# dcc_block_detector.net
KiCad netlist of a schematic drawn in EAGLE
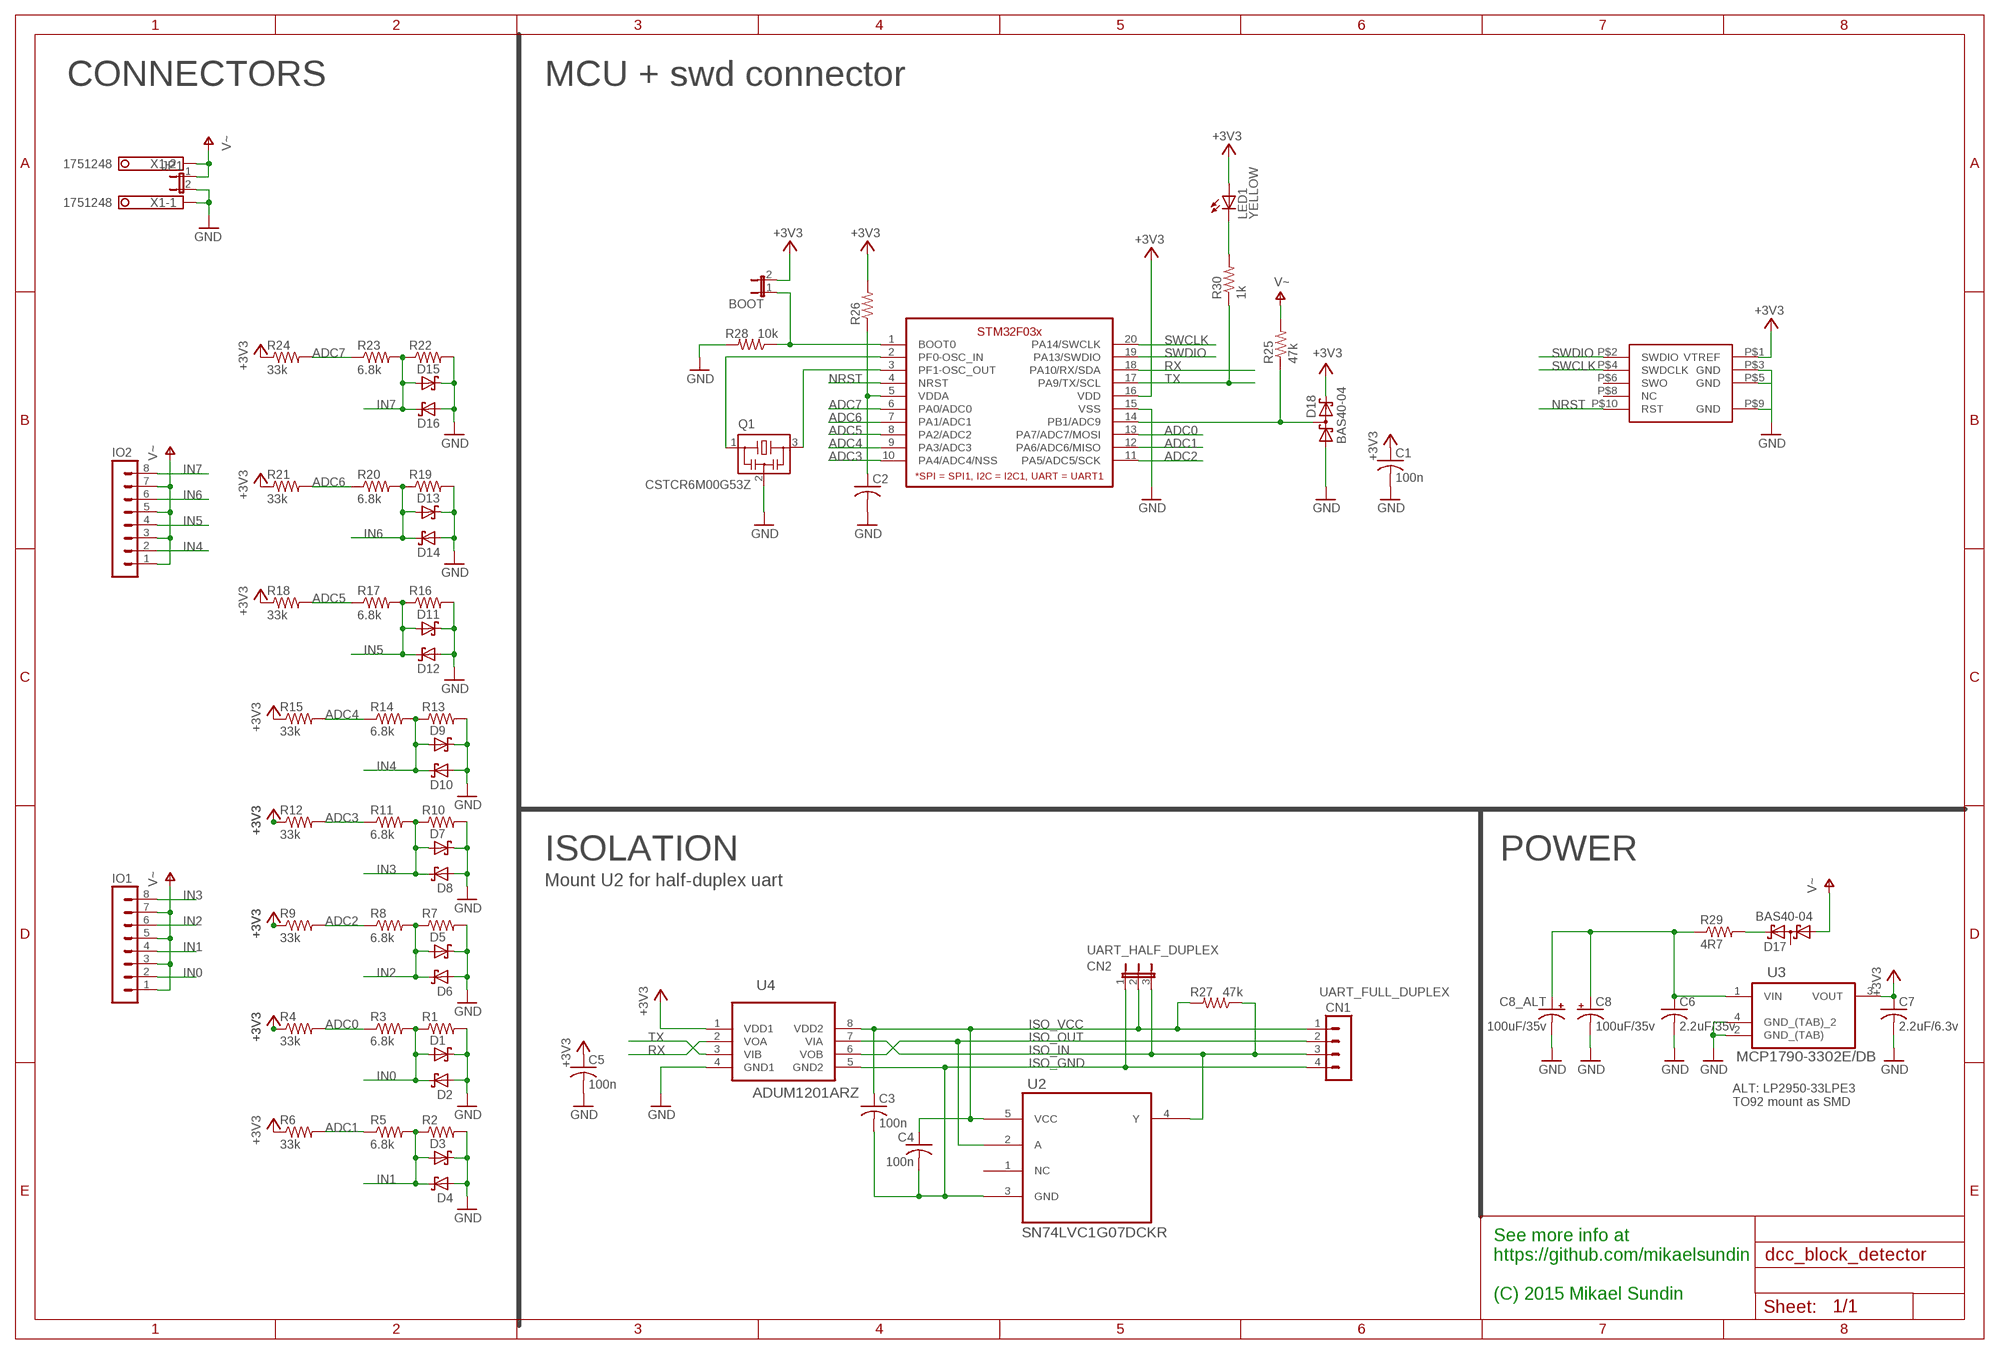
[diagram p0: schematic, sheet 1]

(export (version "E")
  (design (tool "Eeschema 10.0.6"))
  (components
    (comp (ref "BOOT")
      (value "JP1E")
      (footprint "eagle-import:JP1")
      (libsource (lib "eagle-import") (part "JP1E"))
    )
    (comp (ref "C1")
      (value "100n")
      (footprint "eagle-import:C0603")
      (libsource (lib "eagle-import") (part "C-USC0603"))
    )
    (comp (ref "C2")
      (value "C-USC0603")
      (footprint "eagle-import:C0603")
      (libsource (lib "eagle-import") (part "C-USC0603"))
    )
    (comp (ref "C3")
      (value "100n")
      (footprint "eagle-import:C0603")
      (libsource (lib "eagle-import") (part "C-USC0603"))
    )
    (comp (ref "C4")
      (value "100n")
      (footprint "eagle-import:C0603")
      (libsource (lib "eagle-import") (part "C-USC0603"))
    )
    (comp (ref "C5")
      (value "100n")
      (footprint "eagle-import:C0603")
      (libsource (lib "eagle-import") (part "C-USC0603"))
    )
    (comp (ref "C6")
      (value "2.2uF/35v")
      (footprint "eagle-import:C0805")
      (libsource (lib "eagle-import") (part "C-USC0805"))
    )
    (comp (ref "C7")
      (value "2.2uF/6.3v")
      (footprint "eagle-import:C0805")
      (libsource (lib "eagle-import") (part "C-USC0805"))
    )
    (comp (ref "C8")
      (value "100uF/35v")
      (footprint "eagle-import:UD-6,3X7,7_NICHICON")
      (libsource (lib "eagle-import") (part "CPOL-USUD-6,3X7,7"))
    )
    (comp (ref "C8_ALT")
      (value "100uF/35v")
      (footprint "eagle-import:E2,5-6")
      (libsource (lib "eagle-import") (part "CPOL-USE2.5-6"))
    )
    (comp (ref "CN1")
      (value "UART_FULL_DUPLEX")
      (footprint "eagle-import:MA04-1")
      (libsource (lib "eagle-import") (part "MA04-1"))
    )
    (comp (ref "CN2")
      (value "UART_HALF_DUPLEX")
      (footprint "eagle-import:JP2")
      (libsource (lib "eagle-import") (part "JP2E"))
    )
    (comp (ref "D1")
      (value "SCHOTTKY-DIODESMC")
      (footprint "eagle-import:SMC")
      (libsource (lib "eagle-import") (part "SCHOTTKY-DIODESMC"))
    )
    (comp (ref "D2")
      (value "SCHOTTKY-DIODESMC")
      (footprint "eagle-import:SMC")
      (libsource (lib "eagle-import") (part "SCHOTTKY-DIODESMC"))
    )
    (comp (ref "D3")
      (value "SCHOTTKY-DIODESMC")
      (footprint "eagle-import:SMC")
      (libsource (lib "eagle-import") (part "SCHOTTKY-DIODESMC"))
    )
    (comp (ref "D4")
      (value "SCHOTTKY-DIODESMC")
      (footprint "eagle-import:SMC")
      (libsource (lib "eagle-import") (part "SCHOTTKY-DIODESMC"))
    )
    (comp (ref "D5")
      (value "SCHOTTKY-DIODESMC")
      (footprint "eagle-import:SMC")
      (libsource (lib "eagle-import") (part "SCHOTTKY-DIODESMC"))
    )
    (comp (ref "D6")
      (value "SCHOTTKY-DIODESMC")
      (footprint "eagle-import:SMC")
      (libsource (lib "eagle-import") (part "SCHOTTKY-DIODESMC"))
    )
    (comp (ref "D7")
      (value "SCHOTTKY-DIODESMC")
      (footprint "eagle-import:SMC")
      (libsource (lib "eagle-import") (part "SCHOTTKY-DIODESMC"))
    )
    (comp (ref "D8")
      (value "SCHOTTKY-DIODESMC")
      (footprint "eagle-import:SMC")
      (libsource (lib "eagle-import") (part "SCHOTTKY-DIODESMC"))
    )
    (comp (ref "D9")
      (value "SCHOTTKY-DIODESMC")
      (footprint "eagle-import:SMC")
      (libsource (lib "eagle-import") (part "SCHOTTKY-DIODESMC"))
    )
    (comp (ref "D10")
      (value "SCHOTTKY-DIODESMC")
      (footprint "eagle-import:SMC")
      (libsource (lib "eagle-import") (part "SCHOTTKY-DIODESMC"))
    )
    (comp (ref "D11")
      (value "SCHOTTKY-DIODESMC")
      (footprint "eagle-import:SMC")
      (libsource (lib "eagle-import") (part "SCHOTTKY-DIODESMC"))
    )
    (comp (ref "D12")
      (value "SCHOTTKY-DIODESMC")
      (footprint "eagle-import:SMC")
      (libsource (lib "eagle-import") (part "SCHOTTKY-DIODESMC"))
    )
    (comp (ref "D13")
      (value "SCHOTTKY-DIODESMC")
      (footprint "eagle-import:SMC")
      (libsource (lib "eagle-import") (part "SCHOTTKY-DIODESMC"))
    )
    (comp (ref "D14")
      (value "SCHOTTKY-DIODESMC")
      (footprint "eagle-import:SMC")
      (libsource (lib "eagle-import") (part "SCHOTTKY-DIODESMC"))
    )
    (comp (ref "D15")
      (value "SCHOTTKY-DIODESMC")
      (footprint "eagle-import:SMC")
      (libsource (lib "eagle-import") (part "SCHOTTKY-DIODESMC"))
    )
    (comp (ref "D16")
      (value "SCHOTTKY-DIODESMC")
      (footprint "eagle-import:SMC")
      (libsource (lib "eagle-import") (part "SCHOTTKY-DIODESMC"))
    )
    (comp (ref "D17")
      (value "BAS40-04")
      (footprint "eagle-import:SOT23")
      (libsource (lib "eagle-import") (part "BAS40-04"))
    )
    (comp (ref "D18")
      (value "BAS40-04")
      (footprint "eagle-import:SOT23")
      (libsource (lib "eagle-import") (part "BAS40-04"))
    )
    (comp (ref "IO1")
      (value "MA08-1W")
      (footprint "eagle-import:MA08-1W")
      (libsource (lib "eagle-import") (part "MA08-1W"))
    )
    (comp (ref "IO2")
      (value "MA08-1W")
      (footprint "eagle-import:MA08-1W")
      (libsource (lib "eagle-import") (part "MA08-1W"))
    )
    (comp (ref "JP1")
      (value "JP1E")
      (footprint "eagle-import:JP1")
      (libsource (lib "eagle-import") (part "JP1E"))
    )
    (comp (ref "LED1")
      (value "YELLOW")
      (footprint "eagle-import:CHIPLED_0603")
      (libsource (lib "eagle-import") (part "LEDCHIPLED_0603"))
    )
    (comp (ref "Q1")
      (value "CSTCR6M00G53Z")
      (footprint "eagle-import:CSTER12M")
      (fields (field (name "MPN") "CSTCC12M0"))
      (libsource (lib "eagle-import") (part "CSTCR6M00G53Z"))
    )
    (comp (ref "R1")
      (value "R-US_R1206")
      (footprint "eagle-import:R1206")
      (libsource (lib "eagle-import") (part "R-US_R1206"))
    )
    (comp (ref "R2")
      (value "R-US_R1206")
      (footprint "eagle-import:R1206")
      (libsource (lib "eagle-import") (part "R-US_R1206"))
    )
    (comp (ref "R3")
      (value "6.8k")
      (footprint "eagle-import:R0603")
      (libsource (lib "eagle-import") (part "R-US_R0603"))
    )
    (comp (ref "R4")
      (value "33k")
      (footprint "eagle-import:R0603")
      (libsource (lib "eagle-import") (part "R-US_R0603"))
    )
    (comp (ref "R5")
      (value "6.8k")
      (footprint "eagle-import:R0603")
      (libsource (lib "eagle-import") (part "R-US_R0603"))
    )
    (comp (ref "R6")
      (value "33k")
      (footprint "eagle-import:R0603")
      (libsource (lib "eagle-import") (part "R-US_R0603"))
    )
    (comp (ref "R7")
      (value "R-US_R1206")
      (footprint "eagle-import:R1206")
      (libsource (lib "eagle-import") (part "R-US_R1206"))
    )
    (comp (ref "R8")
      (value "6.8k")
      (footprint "eagle-import:R0603")
      (libsource (lib "eagle-import") (part "R-US_R0603"))
    )
    (comp (ref "R9")
      (value "33k")
      (footprint "eagle-import:R0603")
      (libsource (lib "eagle-import") (part "R-US_R0603"))
    )
    (comp (ref "R10")
      (value "R-US_R1206")
      (footprint "eagle-import:R1206")
      (libsource (lib "eagle-import") (part "R-US_R1206"))
    )
    (comp (ref "R11")
      (value "6.8k")
      (footprint "eagle-import:R0603")
      (libsource (lib "eagle-import") (part "R-US_R0603"))
    )
    (comp (ref "R12")
      (value "33k")
      (footprint "eagle-import:R0603")
      (libsource (lib "eagle-import") (part "R-US_R0603"))
    )
    (comp (ref "R13")
      (value "R-US_R1206")
      (footprint "eagle-import:R1206")
      (libsource (lib "eagle-import") (part "R-US_R1206"))
    )
    (comp (ref "R14")
      (value "6.8k")
      (footprint "eagle-import:R0603")
      (libsource (lib "eagle-import") (part "R-US_R0603"))
    )
    (comp (ref "R15")
      (value "33k")
      (footprint "eagle-import:R0603")
      (libsource (lib "eagle-import") (part "R-US_R0603"))
    )
    (comp (ref "R16")
      (value "R-US_R1206")
      (footprint "eagle-import:R1206")
      (libsource (lib "eagle-import") (part "R-US_R1206"))
    )
    (comp (ref "R17")
      (value "6.8k")
      (footprint "eagle-import:R0603")
      (libsource (lib "eagle-import") (part "R-US_R0603"))
    )
    (comp (ref "R18")
      (value "33k")
      (footprint "eagle-import:R0603")
      (libsource (lib "eagle-import") (part "R-US_R0603"))
    )
    (comp (ref "R19")
      (value "R-US_R1206")
      (footprint "eagle-import:R1206")
      (libsource (lib "eagle-import") (part "R-US_R1206"))
    )
    (comp (ref "R20")
      (value "6.8k")
      (footprint "eagle-import:R0603")
      (libsource (lib "eagle-import") (part "R-US_R0603"))
    )
    (comp (ref "R21")
      (value "33k")
      (footprint "eagle-import:R0603")
      (libsource (lib "eagle-import") (part "R-US_R0603"))
    )
    (comp (ref "R22")
      (value "R-US_R1206")
      (footprint "eagle-import:R1206")
      (libsource (lib "eagle-import") (part "R-US_R1206"))
    )
    (comp (ref "R23")
      (value "6.8k")
      (footprint "eagle-import:R0603")
      (libsource (lib "eagle-import") (part "R-US_R0603"))
    )
    (comp (ref "R24")
      (value "33k")
      (footprint "eagle-import:R0603")
      (libsource (lib "eagle-import") (part "R-US_R0603"))
    )
    (comp (ref "R25")
      (value "47k")
      (footprint "eagle-import:R0603")
      (libsource (lib "eagle-import") (part "R-US_R0603"))
    )
    (comp (ref "R26")
      (value "R-US_R0603")
      (footprint "eagle-import:R0603")
      (libsource (lib "eagle-import") (part "R-US_R0603"))
    )
    (comp (ref "R27")
      (value "47k")
      (footprint "eagle-import:R0603")
      (libsource (lib "eagle-import") (part "R-US_R0603"))
    )
    (comp (ref "R28")
      (value "10k")
      (footprint "eagle-import:R0603")
      (libsource (lib "eagle-import") (part "R-US_R0603"))
    )
    (comp (ref "R29")
      (value "4R7")
      (footprint "eagle-import:R1206")
      (libsource (lib "eagle-import") (part "R-US_R1206"))
    )
    (comp (ref "R30")
      (value "1k")
      (footprint "eagle-import:R0603")
      (libsource (lib "eagle-import") (part "R-US_R0603"))
    )
    (comp (ref "U$1")
      (value "STM32F03X_TSSOP20")
      (footprint "eagle-import:STM32F03X_TSSOP20")
      (libsource (lib "eagle-import") (part "STM32F03X_TSSOP20"))
    )
    (comp (ref "U$2")
      (value "SWD")
      (footprint "eagle-import:ARM_SWD_2X5")
      (libsource (lib "eagle-import") (part "ARM_SWD_2X5"))
    )
    (comp (ref "U2")
      (value "SN74LVC1G07DCKR")
      (footprint "eagle-import:SOT65P210X110-5N")
      (libsource (lib "eagle-import") (part "SN74LVC1G07DCKR"))
    )
    (comp (ref "U3")
      (value "MCP1790-3302E/DB")
      (footprint "eagle-import:SOT230P700X180-4N")
      (libsource (lib "eagle-import") (part "MCP1790-3302E/DB"))
    )
    (comp (ref "U4")
      (value "ADUM1201ARZ")
      (footprint "eagle-import:SOIC127P600X175-8N")
      (libsource (lib "eagle-import") (part "ADUM1201ARZ"))
    )
    (comp (ref "X1")
      (value "1751248")
      (footprint "eagle-import:1751248")
      (libsource (lib "eagle-import") (part "1751248"))
    )
  )
  (nets
    (net (code "1") (name "+3V3") (class "Default")
      (node (ref "BOOT") (pin "2") (pinfunction "2_2") (pintype "passive"))
      (node (ref "C1") (pin "1") (pinfunction "1_1") (pintype "passive"))
      (node (ref "C5") (pin "1") (pinfunction "1_1") (pintype "passive"))
      (node (ref "C7") (pin "1") (pinfunction "1_1") (pintype "passive"))
      (node (ref "D18") (pin "2") (pinfunction "C2_2") (pintype "passive"))
      (node (ref "LED1") (pin "A") (pinfunction "A_A") (pintype "passive"))
      (node (ref "R12") (pin "1") (pinfunction "1_1") (pintype "passive"))
      (node (ref "R15") (pin "1") (pinfunction "1_1") (pintype "passive"))
      (node (ref "R18") (pin "1") (pinfunction "1_1") (pintype "passive"))
      (node (ref "R21") (pin "1") (pinfunction "1_1") (pintype "passive"))
      (node (ref "R24") (pin "1") (pinfunction "1_1") (pintype "passive"))
      (node (ref "R26") (pin "2") (pinfunction "2_2") (pintype "passive"))
      (node (ref "R4") (pin "1") (pinfunction "1_1") (pintype "passive"))
      (node (ref "R6") (pin "1") (pinfunction "1_1") (pintype "passive"))
      (node (ref "R9") (pin "1") (pinfunction "1_1") (pintype "passive"))
      (node (ref "U$1") (pin "16") (pinfunction "VDD_16") (pintype "output"))
      (node (ref "U$2") (pin "P$1") (pinfunction "VTREF_P$1") (pintype "bidirectional"))
      (node (ref "U3") (pin "3") (pinfunction "VOUT_3") (pintype "output"))
      (node (ref "U4") (pin "1") (pinfunction "VDD1_1") (pintype "power_in"))
    )
    (net (code "2") (name "/ADC0") (class "Default")
      (node (ref "R3") (pin "1") (pinfunction "1_1") (pintype "passive"))
      (node (ref "R4") (pin "2") (pinfunction "2_2") (pintype "passive"))
      (node (ref "U$1") (pin "13") (pinfunction "PA7/ADC7/MOSI_13") (pintype "output"))
    )
    (net (code "3") (name "/ADC1") (class "Default")
      (node (ref "R5") (pin "1") (pinfunction "1_1") (pintype "passive"))
      (node (ref "R6") (pin "2") (pinfunction "2_2") (pintype "passive"))
      (node (ref "U$1") (pin "12") (pinfunction "PA6/ADC6/MISO_12") (pintype "output"))
    )
    (net (code "4") (name "/ADC2") (class "Default")
      (node (ref "R8") (pin "1") (pinfunction "1_1") (pintype "passive"))
      (node (ref "R9") (pin "2") (pinfunction "2_2") (pintype "passive"))
      (node (ref "U$1") (pin "11") (pinfunction "PA5/ADC5/SCK_11") (pintype "output"))
    )
    (net (code "5") (name "/ADC3") (class "Default")
      (node (ref "R11") (pin "1") (pinfunction "1_1") (pintype "passive"))
      (node (ref "R12") (pin "2") (pinfunction "2_2") (pintype "passive"))
      (node (ref "U$1") (pin "10") (pinfunction "PA4/ADC4/NSS_10") (pintype "output"))
    )
    (net (code "6") (name "/ADC4") (class "Default")
      (node (ref "R14") (pin "1") (pinfunction "1_1") (pintype "passive"))
      (node (ref "R15") (pin "2") (pinfunction "2_2") (pintype "passive"))
      (node (ref "U$1") (pin "9") (pinfunction "PA3/ADC3_9") (pintype "output"))
    )
    (net (code "7") (name "/ADC5") (class "Default")
      (node (ref "R17") (pin "1") (pinfunction "1_1") (pintype "passive"))
      (node (ref "R18") (pin "2") (pinfunction "2_2") (pintype "passive"))
      (node (ref "U$1") (pin "8") (pinfunction "PA2/ADC2_8") (pintype "output"))
    )
    (net (code "8") (name "/ADC6") (class "Default")
      (node (ref "R20") (pin "1") (pinfunction "1_1") (pintype "passive"))
      (node (ref "R21") (pin "2") (pinfunction "2_2") (pintype "passive"))
      (node (ref "U$1") (pin "7") (pinfunction "PA1/ADC1_7") (pintype "output"))
    )
    (net (code "9") (name "/ADC7") (class "Default")
      (node (ref "R23") (pin "1") (pinfunction "1_1") (pintype "passive"))
      (node (ref "R24") (pin "2") (pinfunction "2_2") (pintype "passive"))
      (node (ref "U$1") (pin "6") (pinfunction "PA0/ADC0_6") (pintype "output"))
    )
    (net (code "10") (name "/IN0") (class "Default")
      (node (ref "D1") (pin "A") (pinfunction "A_A") (pintype "passive"))
      (node (ref "D2") (pin "C") (pinfunction "C_C") (pintype "passive"))
      (node (ref "IO1") (pin "2") (pinfunction "2_2") (pintype "passive"))
      (node (ref "R1") (pin "1") (pinfunction "1_1") (pintype "passive"))
      (node (ref "R3") (pin "2") (pinfunction "2_2") (pintype "passive"))
    )
    (net (code "11") (name "/IN1") (class "Default")
      (node (ref "D3") (pin "A") (pinfunction "A_A") (pintype "passive"))
      (node (ref "D4") (pin "C") (pinfunction "C_C") (pintype "passive"))
      (node (ref "IO1") (pin "4") (pinfunction "4_4") (pintype "passive"))
      (node (ref "R2") (pin "1") (pinfunction "1_1") (pintype "passive"))
      (node (ref "R5") (pin "2") (pinfunction "2_2") (pintype "passive"))
    )
    (net (code "12") (name "/IN2") (class "Default")
      (node (ref "D5") (pin "A") (pinfunction "A_A") (pintype "passive"))
      (node (ref "D6") (pin "C") (pinfunction "C_C") (pintype "passive"))
      (node (ref "IO1") (pin "6") (pinfunction "6_6") (pintype "passive"))
      (node (ref "R7") (pin "1") (pinfunction "1_1") (pintype "passive"))
      (node (ref "R8") (pin "2") (pinfunction "2_2") (pintype "passive"))
    )
    (net (code "13") (name "/IN3") (class "Default")
      (node (ref "D7") (pin "A") (pinfunction "A_A") (pintype "passive"))
      (node (ref "D8") (pin "C") (pinfunction "C_C") (pintype "passive"))
      (node (ref "IO1") (pin "8") (pinfunction "8_8") (pintype "passive"))
      (node (ref "R10") (pin "1") (pinfunction "1_1") (pintype "passive"))
      (node (ref "R11") (pin "2") (pinfunction "2_2") (pintype "passive"))
    )
    (net (code "14") (name "/IN4") (class "Default")
      (node (ref "D10") (pin "C") (pinfunction "C_C") (pintype "passive"))
      (node (ref "D9") (pin "A") (pinfunction "A_A") (pintype "passive"))
      (node (ref "IO2") (pin "2") (pinfunction "2_2") (pintype "passive"))
      (node (ref "R13") (pin "1") (pinfunction "1_1") (pintype "passive"))
      (node (ref "R14") (pin "2") (pinfunction "2_2") (pintype "passive"))
    )
    (net (code "15") (name "/IN5") (class "Default")
      (node (ref "D11") (pin "A") (pinfunction "A_A") (pintype "passive"))
      (node (ref "D12") (pin "C") (pinfunction "C_C") (pintype "passive"))
      (node (ref "IO2") (pin "4") (pinfunction "4_4") (pintype "passive"))
      (node (ref "R16") (pin "1") (pinfunction "1_1") (pintype "passive"))
      (node (ref "R17") (pin "2") (pinfunction "2_2") (pintype "passive"))
    )
    (net (code "16") (name "/IN6") (class "Default")
      (node (ref "D13") (pin "A") (pinfunction "A_A") (pintype "passive"))
      (node (ref "D14") (pin "C") (pinfunction "C_C") (pintype "passive"))
      (node (ref "IO2") (pin "6") (pinfunction "6_6") (pintype "passive"))
      (node (ref "R19") (pin "1") (pinfunction "1_1") (pintype "passive"))
      (node (ref "R20") (pin "2") (pinfunction "2_2") (pintype "passive"))
    )
    (net (code "17") (name "/IN7") (class "Default")
      (node (ref "D15") (pin "A") (pinfunction "A_A") (pintype "passive"))
      (node (ref "D16") (pin "C") (pinfunction "C_C") (pintype "passive"))
      (node (ref "IO2") (pin "8") (pinfunction "8_8") (pintype "passive"))
      (node (ref "R22") (pin "1") (pinfunction "1_1") (pintype "passive"))
      (node (ref "R23") (pin "2") (pinfunction "2_2") (pintype "passive"))
    )
    (net (code "18") (name "/ISO_GND") (class "Default")
      (node (ref "C3") (pin "2") (pinfunction "2_2") (pintype "passive"))
      (node (ref "C4") (pin "2") (pinfunction "2_2") (pintype "passive"))
      (node (ref "CN1") (pin "4") (pinfunction "4_4") (pintype "passive"))
      (node (ref "CN2") (pin "1") (pinfunction "1_1") (pintype "passive"))
      (node (ref "U2") (pin "3") (pinfunction "GND_3") (pintype "passive"))
      (node (ref "U4") (pin "5") (pinfunction "GND2_5") (pintype "passive"))
    )
    (net (code "19") (name "/ISO_IN") (class "Default")
      (node (ref "CN1") (pin "3") (pinfunction "3_3") (pintype "passive"))
      (node (ref "CN2") (pin "3") (pinfunction "3_3") (pintype "passive"))
      (node (ref "R27") (pin "1") (pinfunction "1_1") (pintype "passive"))
      (node (ref "U2") (pin "4") (pinfunction "Y_4") (pintype "output"))
      (node (ref "U4") (pin "7") (pinfunction "VIA_7") (pintype "input"))
    )
    (net (code "20") (name "/ISO_OUT") (class "Default")
      (node (ref "CN1") (pin "2") (pinfunction "2_2") (pintype "passive"))
      (node (ref "U2") (pin "2") (pinfunction "A_2") (pintype "input"))
      (node (ref "U4") (pin "6") (pinfunction "VOB_6") (pintype "output"))
    )
    (net (code "21") (name "/ISO_VCC") (class "Default")
      (node (ref "C3") (pin "1") (pinfunction "1_1") (pintype "passive"))
      (node (ref "C4") (pin "1") (pinfunction "1_1") (pintype "passive"))
      (node (ref "CN1") (pin "1") (pinfunction "1_1") (pintype "passive"))
      (node (ref "CN2") (pin "2") (pinfunction "2_2") (pintype "passive"))
      (node (ref "R27") (pin "2") (pinfunction "2_2") (pintype "passive"))
      (node (ref "U2") (pin "5") (pinfunction "VCC_5") (pintype "power_in"))
      (node (ref "U4") (pin "8") (pinfunction "VDD2_8") (pintype "power_in"))
    )
    (net (code "22") (name "/NRST") (class "Default")
      (node (ref "U$1") (pin "4") (pinfunction "NRST_4") (pintype "output"))
      (node (ref "U$2") (pin "P$10") (pinfunction "RST_P$10") (pintype "bidirectional"))
    )
    (net (code "23") (name "/RX") (class "Default")
      (node (ref "U$1") (pin "18") (pinfunction "PA10/RX/SDA_18") (pintype "output"))
      (node (ref "U4") (pin "2") (pinfunction "VOA_2") (pintype "output"))
    )
    (net (code "24") (name "/SWCLK") (class "Default")
      (node (ref "U$1") (pin "20") (pinfunction "PA14/SWCLK_20") (pintype "output"))
      (node (ref "U$2") (pin "P$4") (pinfunction "SWDCLK_P$4") (pintype "bidirectional"))
    )
    (net (code "25") (name "/SWDIO") (class "Default")
      (node (ref "U$1") (pin "19") (pinfunction "PA13/SWDIO_19") (pintype "output"))
      (node (ref "U$2") (pin "P$2") (pinfunction "SWDIO_P$2") (pintype "bidirectional"))
    )
    (net (code "26") (name "/TX") (class "Default")
      (node (ref "R30") (pin "1") (pinfunction "1_1") (pintype "passive"))
      (node (ref "U$1") (pin "17") (pinfunction "PA9/TX/SCL_17") (pintype "output"))
      (node (ref "U4") (pin "3") (pinfunction "VIB_3") (pintype "input"))
    )
    (net (code "27") (name "GND") (class "Default")
      (node (ref "C1") (pin "2") (pinfunction "2_2") (pintype "passive"))
      (node (ref "C2") (pin "2") (pinfunction "2_2") (pintype "passive"))
      (node (ref "C5") (pin "2") (pinfunction "2_2") (pintype "passive"))
      (node (ref "C6") (pin "2") (pinfunction "2_2") (pintype "passive"))
      (node (ref "C7") (pin "2") (pinfunction "2_2") (pintype "passive"))
      (node (ref "C8") (pin "-") (pinfunction "-_-") (pintype "passive"))
      (node (ref "C8_ALT") (pin "-") (pinfunction "-_-") (pintype "passive"))
      (node (ref "D1") (pin "C") (pinfunction "C_C") (pintype "passive"))
      (node (ref "D10") (pin "A") (pinfunction "A_A") (pintype "passive"))
      (node (ref "D11") (pin "C") (pinfunction "C_C") (pintype "passive"))
      (node (ref "D12") (pin "A") (pinfunction "A_A") (pintype "passive"))
      (node (ref "D13") (pin "C") (pinfunction "C_C") (pintype "passive"))
      (node (ref "D14") (pin "A") (pinfunction "A_A") (pintype "passive"))
      (node (ref "D15") (pin "C") (pinfunction "C_C") (pintype "passive"))
      (node (ref "D16") (pin "A") (pinfunction "A_A") (pintype "passive"))
      (node (ref "D18") (pin "1") (pinfunction "A1_1") (pintype "passive"))
      (node (ref "D2") (pin "A") (pinfunction "A_A") (pintype "passive"))
      (node (ref "D3") (pin "C") (pinfunction "C_C") (pintype "passive"))
      (node (ref "D4") (pin "A") (pinfunction "A_A") (pintype "passive"))
      (node (ref "D5") (pin "C") (pinfunction "C_C") (pintype "passive"))
      (node (ref "D6") (pin "A") (pinfunction "A_A") (pintype "passive"))
      (node (ref "D7") (pin "C") (pinfunction "C_C") (pintype "passive"))
      (node (ref "D8") (pin "A") (pinfunction "A_A") (pintype "passive"))
      (node (ref "D9") (pin "C") (pinfunction "C_C") (pintype "passive"))
      (node (ref "JP1") (pin "2") (pinfunction "2_2") (pintype "passive"))
      (node (ref "Q1") (pin "2") (pinfunction "2_2") (pintype "passive"))
      (node (ref "R1") (pin "2") (pinfunction "2_2") (pintype "passive"))
      (node (ref "R10") (pin "2") (pinfunction "2_2") (pintype "passive"))
      (node (ref "R13") (pin "2") (pinfunction "2_2") (pintype "passive"))
      (node (ref "R16") (pin "2") (pinfunction "2_2") (pintype "passive"))
      (node (ref "R19") (pin "2") (pinfunction "2_2") (pintype "passive"))
      (node (ref "R2") (pin "2") (pinfunction "2_2") (pintype "passive"))
      (node (ref "R22") (pin "2") (pinfunction "2_2") (pintype "passive"))
      (node (ref "R28") (pin "2") (pinfunction "2_2") (pintype "passive"))
      (node (ref "R7") (pin "2") (pinfunction "2_2") (pintype "passive"))
      (node (ref "U$1") (pin "15") (pinfunction "VSS_15") (pintype "output"))
      (node (ref "U$2") (pin "P$3") (pinfunction "GND_P$3") (pintype "bidirectional"))
      (node (ref "U$2") (pin "P$5") (pinfunction "GND_P$5") (pintype "bidirectional"))
      (node (ref "U$2") (pin "P$9") (pinfunction "GND_P$9") (pintype "bidirectional"))
      (node (ref "U3") (pin "2") (pinfunction "GND_(TAB)_2") (pintype "passive"))
      (node (ref "U3") (pin "4") (pinfunction "GND_(TAB)_2_4") (pintype "passive"))
      (node (ref "U4") (pin "4") (pinfunction "GND1_4") (pintype "passive"))
      (node (ref "X1") (pin "1") (pinfunction "K_1") (pintype "passive"))
    )
    (net (code "28") (name "Net-(D17-C2)") (class "Default")
      (node (ref "D17") (pin "2") (pinfunction "C2_2") (pintype "passive"))
      (node (ref "R29") (pin "2") (pinfunction "2_2") (pintype "passive"))
    )
    (net (code "29") (name "Net-(D18-C1A2)") (class "Default")
      (node (ref "D18") (pin "3") (pinfunction "C1A2_3") (pintype "passive"))
      (node (ref "R25") (pin "1") (pinfunction "1_1") (pintype "passive"))
      (node (ref "U$1") (pin "14") (pinfunction "PB1/ADC9_14") (pintype "output"))
    )
    (net (code "30") (name "Net-(LED1-PadC)") (class "Default")
      (node (ref "LED1") (pin "C") (pinfunction "C_C") (pintype "passive"))
      (node (ref "R30") (pin "2") (pinfunction "2_2") (pintype "passive"))
    )
    (net (code "31") (name "Net-(U$1-BOOT0)") (class "Default")
      (node (ref "BOOT") (pin "1") (pinfunction "1_1") (pintype "passive"))
      (node (ref "R28") (pin "1") (pinfunction "1_1") (pintype "passive"))
      (node (ref "U$1") (pin "1") (pinfunction "BOOT0_1") (pintype "output"))
    )
    (net (code "32") (name "Net-(U$1-PF0-OSC_IN)") (class "Default")
      (node (ref "Q1") (pin "1") (pinfunction "1_1") (pintype "passive"))
      (node (ref "U$1") (pin "2") (pinfunction "PF0-OSC_IN_2") (pintype "output"))
    )
    (net (code "33") (name "Net-(U$1-PF1-OSC_OUT)") (class "Default")
      (node (ref "Q1") (pin "3") (pinfunction "3_3") (pintype "passive"))
      (node (ref "U$1") (pin "3") (pinfunction "PF1-OSC_OUT_3") (pintype "output"))
    )
    (net (code "34") (name "Net-(U$1-VDDA)") (class "Default")
      (node (ref "C2") (pin "1") (pinfunction "1_1") (pintype "passive"))
      (node (ref "R26") (pin "1") (pinfunction "1_1") (pintype "passive"))
      (node (ref "U$1") (pin "5") (pinfunction "VDDA_5") (pintype "output"))
    )
    (net (code "35") (name "Net-(U3-VIN)") (class "Default")
      (node (ref "C6") (pin "1") (pinfunction "1_1") (pintype "passive"))
      (node (ref "C8") (pin "+") (pinfunction "+_+") (pintype "passive"))
      (node (ref "C8_ALT") (pin "+") (pinfunction "+_+") (pintype "passive"))
      (node (ref "R29") (pin "1") (pinfunction "1_1") (pintype "passive"))
      (node (ref "U3") (pin "1") (pinfunction "VIN_1") (pintype "input"))
    )
    (net (code "36") (name "V~") (class "Default")
      (node (ref "D17") (pin "1") (pinfunction "A1_1") (pintype "passive"))
      (node (ref "IO1") (pin "1") (pinfunction "1_1") (pintype "passive"))
      (node (ref "IO1") (pin "3") (pinfunction "3_3") (pintype "passive"))
      (node (ref "IO1") (pin "5") (pinfunction "5_5") (pintype "passive"))
      (node (ref "IO1") (pin "7") (pinfunction "7_7") (pintype "passive"))
      (node (ref "IO2") (pin "1") (pinfunction "1_1") (pintype "passive"))
      (node (ref "IO2") (pin "3") (pinfunction "3_3") (pintype "passive"))
      (node (ref "IO2") (pin "5") (pinfunction "5_5") (pintype "passive"))
      (node (ref "IO2") (pin "7") (pinfunction "7_7") (pintype "passive"))
      (node (ref "JP1") (pin "1") (pinfunction "1_1") (pintype "passive"))
      (node (ref "R25") (pin "2") (pinfunction "2_2") (pintype "passive"))
      (node (ref "X1") (pin "2") (pinfunction "K_2") (pintype "passive"))
    )
    (net (code "37") (name "unconnected-(D17-C1A2-Pad3)") (class "Default")
      (node (ref "D17") (pin "3") (pinfunction "C1A2_3") (pintype "passive"))
    )
    (net (code "38") (name "unconnected-(U$2-NC-PadP$8)") (class "Default")
      (node (ref "U$2") (pin "P$8") (pinfunction "NC_P$8") (pintype "bidirectional"))
    )
    (net (code "39") (name "unconnected-(U$2-SWO-PadP$6)") (class "Default")
      (node (ref "U$2") (pin "P$6") (pinfunction "SWO_P$6") (pintype "bidirectional"))
    )
    (net (code "40") (name "unconnected-(U2-NC-Pad1)") (class "Default")
      (node (ref "U2") (pin "1") (pinfunction "NC_1") (pintype "no_connect"))
    )
  )
)
